# alarma-ESP32-30.net
KiCad netlist of a schematic drawn in EAGLE
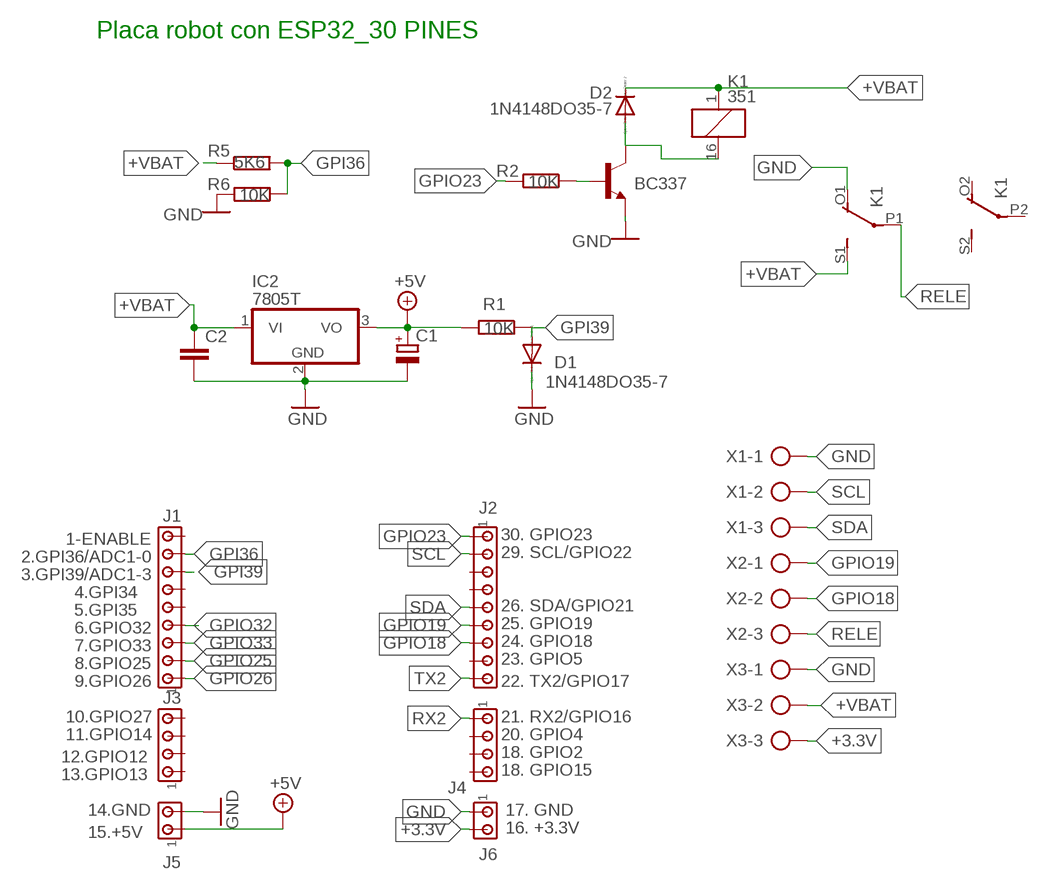
[diagram p0: schematic, sheet 1]

(export (version "E")
  (design (tool "Eeschema 10.0.6"))
  (components
    (comp (ref "BC337")
      (value "BC337-16-NPN-TO92-CBE")
      (footprint "eagle-import:TO92-CBE")
      (libsource (lib "eagle-import") (part "-NPN-TO92-CBEBC337-16"))
    )
    (comp (ref "C1")
      (value "CPOL-EUE2.5-6")
      (footprint "eagle-import:E2,5-6")
      (libsource (lib "eagle-import") (part "CPOL-EUE2.5-6"))
    )
    (comp (ref "C2")
      (value "C-EU025-025X050")
      (footprint "eagle-import:C025-025X050")
      (libsource (lib "eagle-import") (part "C-EU025-025X050"))
    )
    (comp (ref "D1")
      (value "1N4148DO35-7")
      (footprint "eagle-import:DO35-7")
      (libsource (lib "eagle-import") (part "1N4148DO35-7"))
    )
    (comp (ref "D2")
      (value "1N4148DO35-7")
      (footprint "eagle-import:DO35-7")
      (libsource (lib "eagle-import") (part "1N4148DO35-7"))
    )
    (comp (ref "IC2")
      (value "7805T")
      (footprint "eagle-import:TO220H")
      (libsource (lib "eagle-import") (part "78T05"))
    )
    (comp (ref "J1")
      (value "MTA09-100")
      (footprint "eagle-import:10X09MTA")
      (libsource (lib "eagle-import") (part "MTA09-100"))
    )
    (comp (ref "J2")
      (value "MTA09-100")
      (footprint "eagle-import:10X09MTA")
      (libsource (lib "eagle-import") (part "MTA09-100"))
    )
    (comp (ref "J3")
      (value "MTA04-100")
      (footprint "eagle-import:10X04MTA")
      (libsource (lib "eagle-import") (part "MTA04-100"))
    )
    (comp (ref "J4")
      (value "MTA04-100")
      (footprint "eagle-import:10X04MTA")
      (libsource (lib "eagle-import") (part "MTA04-100"))
    )
    (comp (ref "J5")
      (value "MTA02-100")
      (footprint "eagle-import:10X02MTA")
      (libsource (lib "eagle-import") (part "MTA02-100"))
    )
    (comp (ref "J6")
      (value "MTA02-100")
      (footprint "eagle-import:10X02MTA")
      (libsource (lib "eagle-import") (part "MTA02-100"))
    )
    (comp (ref "K1")
      (value "351")
      (footprint "eagle-import:351")
      (libsource (lib "eagle-import") (part "351"))
    )
    (comp (ref "R1")
      (value "10K")
      (footprint "eagle-import:0207_7")
      (libsource (lib "eagle-import") (part "R-EU_0207/7"))
    )
    (comp (ref "R2")
      (value "10K")
      (footprint "eagle-import:0207_15")
      (libsource (lib "eagle-import") (part "R-EU_0207/15"))
    )
    (comp (ref "R5")
      (value "5K6")
      (footprint "eagle-import:0207_7")
      (libsource (lib "eagle-import") (part "R-EU_0207/7"))
    )
    (comp (ref "R6")
      (value "10K")
      (footprint "eagle-import:0207_7")
      (libsource (lib "eagle-import") (part "R-EU_0207/7"))
    )
    (comp (ref "X1")
      (value "AK500/3")
      (footprint "eagle-import:AK500_3")
      (libsource (lib "eagle-import") (part "AK500/3"))
    )
    (comp (ref "X2")
      (value "AK500/3")
      (footprint "eagle-import:AK500_3")
      (libsource (lib "eagle-import") (part "AK500/3"))
    )
    (comp (ref "X3")
      (value "AK500/3")
      (footprint "eagle-import:AK500_3")
      (libsource (lib "eagle-import") (part "AK500/3"))
    )
  )
  (nets
    (net (code "1") (name "+3.3V") (class "Default")
      (node (ref "J6") (pin "2") (pinfunction "2_2") (pintype "passive"))
      (node (ref "X3") (pin "3") (pinfunction "KL_3") (pintype "passive"))
    )
    (net (code "2") (name "+5V") (class "Default")
      (node (ref "C1") (pin "+") (pinfunction "+_+") (pintype "passive"))
      (node (ref "IC2") (pin "3") (pinfunction "VO_3") (pintype "passive"))
      (node (ref "J5") (pin "1") (pinfunction "1_1") (pintype "passive"))
      (node (ref "R1") (pin "2") (pinfunction "2_2") (pintype "passive"))
    )
    (net (code "3") (name "+VBAT") (class "Default")
      (node (ref "C2") (pin "1") (pinfunction "1_1") (pintype "passive"))
      (node (ref "D2") (pin "C") (pinfunction "C_C") (pintype "passive"))
      (node (ref "IC2") (pin "1") (pinfunction "VI_1") (pintype "input"))
      (node (ref "K1") (pin "1") (pinfunction "1_1") (pintype "passive"))
      (node (ref "K1") (pin "S1") (pinfunction "S_S1") (pintype "passive"))
      (node (ref "R5") (pin "1") (pinfunction "1_1") (pintype "passive"))
      (node (ref "X3") (pin "2") (pinfunction "KL_2") (pintype "passive"))
    )
    (net (code "4") (name "GND") (class "Default")
      (node (ref "BC337") (pin "E") (pinfunction "E_E") (pintype "passive"))
      (node (ref "C1") (pin "-") (pinfunction "-_-") (pintype "passive"))
      (node (ref "C2") (pin "2") (pinfunction "2_2") (pintype "passive"))
      (node (ref "D1") (pin "C") (pinfunction "C_C") (pintype "passive"))
      (node (ref "IC2") (pin "2") (pinfunction "GND_2") (pintype "passive"))
      (node (ref "J5") (pin "2") (pinfunction "2_2") (pintype "passive"))
      (node (ref "J6") (pin "1") (pinfunction "1_1") (pintype "passive"))
      (node (ref "K1") (pin "O1") (pinfunction "O_O1") (pintype "passive"))
      (node (ref "R6") (pin "2") (pinfunction "2_2") (pintype "passive"))
      (node (ref "X1") (pin "1") (pinfunction "KL_1") (pintype "passive"))
      (node (ref "X3") (pin "1") (pinfunction "KL_1") (pintype "passive"))
    )
    (net (code "5") (name "GPI36") (class "Default")
      (node (ref "J1") (pin "8") (pinfunction "8_8") (pintype "passive"))
      (node (ref "R5") (pin "2") (pinfunction "2_2") (pintype "passive"))
      (node (ref "R6") (pin "1") (pinfunction "1_1") (pintype "passive"))
    )
    (net (code "6") (name "GPI39") (class "Default")
      (node (ref "D1") (pin "A") (pinfunction "A_A") (pintype "passive"))
      (node (ref "J1") (pin "7") (pinfunction "7_7") (pintype "passive"))
      (node (ref "R1") (pin "1") (pinfunction "1_1") (pintype "passive"))
    )
    (net (code "7") (name "GPIO18") (class "Default")
      (node (ref "J2") (pin "7") (pinfunction "7_7") (pintype "passive"))
      (node (ref "X2") (pin "2") (pinfunction "KL_2") (pintype "passive"))
    )
    (net (code "8") (name "GPIO19") (class "Default")
      (node (ref "J2") (pin "6") (pinfunction "6_6") (pintype "passive"))
      (node (ref "X2") (pin "1") (pinfunction "KL_1") (pintype "passive"))
    )
    (net (code "9") (name "GPIO23") (class "Default")
      (node (ref "J2") (pin "1") (pinfunction "1_1") (pintype "passive"))
      (node (ref "R2") (pin "2") (pinfunction "2_2") (pintype "passive"))
    )
    (net (code "10") (name "GPIO25") (class "Default")
      (node (ref "J1") (pin "2") (pinfunction "2_2") (pintype "passive"))
    )
    (net (code "11") (name "GPIO26") (class "Default")
      (node (ref "J1") (pin "1") (pinfunction "1_1") (pintype "passive"))
    )
    (net (code "12") (name "GPIO32") (class "Default")
      (node (ref "J1") (pin "4") (pinfunction "4_4") (pintype "passive"))
    )
    (net (code "13") (name "GPIO33") (class "Default")
      (node (ref "J1") (pin "3") (pinfunction "3_3") (pintype "passive"))
    )
    (net (code "14") (name "Net-(BC337-PadB)") (class "Default")
      (node (ref "BC337") (pin "B") (pinfunction "B_B") (pintype "passive"))
      (node (ref "R2") (pin "1") (pinfunction "1_1") (pintype "passive"))
    )
    (net (code "15") (name "Net-(K1A-2)") (class "Default")
      (node (ref "BC337") (pin "C") (pinfunction "C_C") (pintype "passive"))
      (node (ref "D2") (pin "A") (pinfunction "A_A") (pintype "passive"))
      (node (ref "K1") (pin "16") (pinfunction "2_16") (pintype "passive"))
    )
    (net (code "16") (name "RELE") (class "Default")
      (node (ref "K1") (pin "P1") (pinfunction "P_P1") (pintype "passive"))
      (node (ref "X2") (pin "3") (pinfunction "KL_3") (pintype "passive"))
    )
    (net (code "17") (name "RX2") (class "Default")
      (node (ref "J4") (pin "1") (pinfunction "1_1") (pintype "passive"))
    )
    (net (code "18") (name "SCL") (class "Default")
      (node (ref "J2") (pin "2") (pinfunction "2_2") (pintype "passive"))
      (node (ref "X1") (pin "2") (pinfunction "KL_2") (pintype "passive"))
    )
    (net (code "19") (name "SDA") (class "Default")
      (node (ref "J2") (pin "5") (pinfunction "5_5") (pintype "passive"))
      (node (ref "X1") (pin "3") (pinfunction "KL_3") (pintype "passive"))
    )
    (net (code "20") (name "TX2") (class "Default")
      (node (ref "J2") (pin "9") (pinfunction "9_9") (pintype "passive"))
    )
    (net (code "21") (name "unconnected-(J1-Pad5)") (class "Default")
      (node (ref "J1") (pin "5") (pinfunction "5_5") (pintype "passive"))
    )
    (net (code "22") (name "unconnected-(J1-Pad6)") (class "Default")
      (node (ref "J1") (pin "6") (pinfunction "6_6") (pintype "passive"))
    )
    (net (code "23") (name "unconnected-(J1-Pad9)") (class "Default")
      (node (ref "J1") (pin "9") (pinfunction "9_9") (pintype "passive"))
    )
    (net (code "24") (name "unconnected-(J2-Pad3)") (class "Default")
      (node (ref "J2") (pin "3") (pinfunction "3_3") (pintype "passive"))
    )
    (net (code "25") (name "unconnected-(J2-Pad4)") (class "Default")
      (node (ref "J2") (pin "4") (pinfunction "4_4") (pintype "passive"))
    )
    (net (code "26") (name "unconnected-(J2-Pad8)") (class "Default")
      (node (ref "J2") (pin "8") (pinfunction "8_8") (pintype "passive"))
    )
    (net (code "27") (name "unconnected-(J3-Pad1)") (class "Default")
      (node (ref "J3") (pin "1") (pinfunction "1_1") (pintype "passive"))
    )
    (net (code "28") (name "unconnected-(J3-Pad2)") (class "Default")
      (node (ref "J3") (pin "2") (pinfunction "2_2") (pintype "passive"))
    )
    (net (code "29") (name "unconnected-(J3-Pad3)") (class "Default")
      (node (ref "J3") (pin "3") (pinfunction "3_3") (pintype "passive"))
    )
    (net (code "30") (name "unconnected-(J3-Pad4)") (class "Default")
      (node (ref "J3") (pin "4") (pinfunction "4_4") (pintype "passive"))
    )
    (net (code "31") (name "unconnected-(J4-Pad2)") (class "Default")
      (node (ref "J4") (pin "2") (pinfunction "2_2") (pintype "passive"))
    )
    (net (code "32") (name "unconnected-(J4-Pad3)") (class "Default")
      (node (ref "J4") (pin "3") (pinfunction "3_3") (pintype "passive"))
    )
    (net (code "33") (name "unconnected-(J4-Pad4)") (class "Default")
      (node (ref "J4") (pin "4") (pinfunction "4_4") (pintype "passive"))
    )
    (net (code "34") (name "unconnected-(K1C-O-PadO2)") (class "Default")
      (node (ref "K1") (pin "O2") (pinfunction "O_O2") (pintype "passive"))
    )
    (net (code "35") (name "unconnected-(K1C-P-PadP2)") (class "Default")
      (node (ref "K1") (pin "P2") (pinfunction "P_P2") (pintype "passive"))
    )
    (net (code "36") (name "unconnected-(K1C-S-PadS2)") (class "Default")
      (node (ref "K1") (pin "S2") (pinfunction "S_S2") (pintype "passive"))
    )
  )
)
